# MODULO_TECLADO.net
KiCad netlist of a schematic drawn in EAGLE
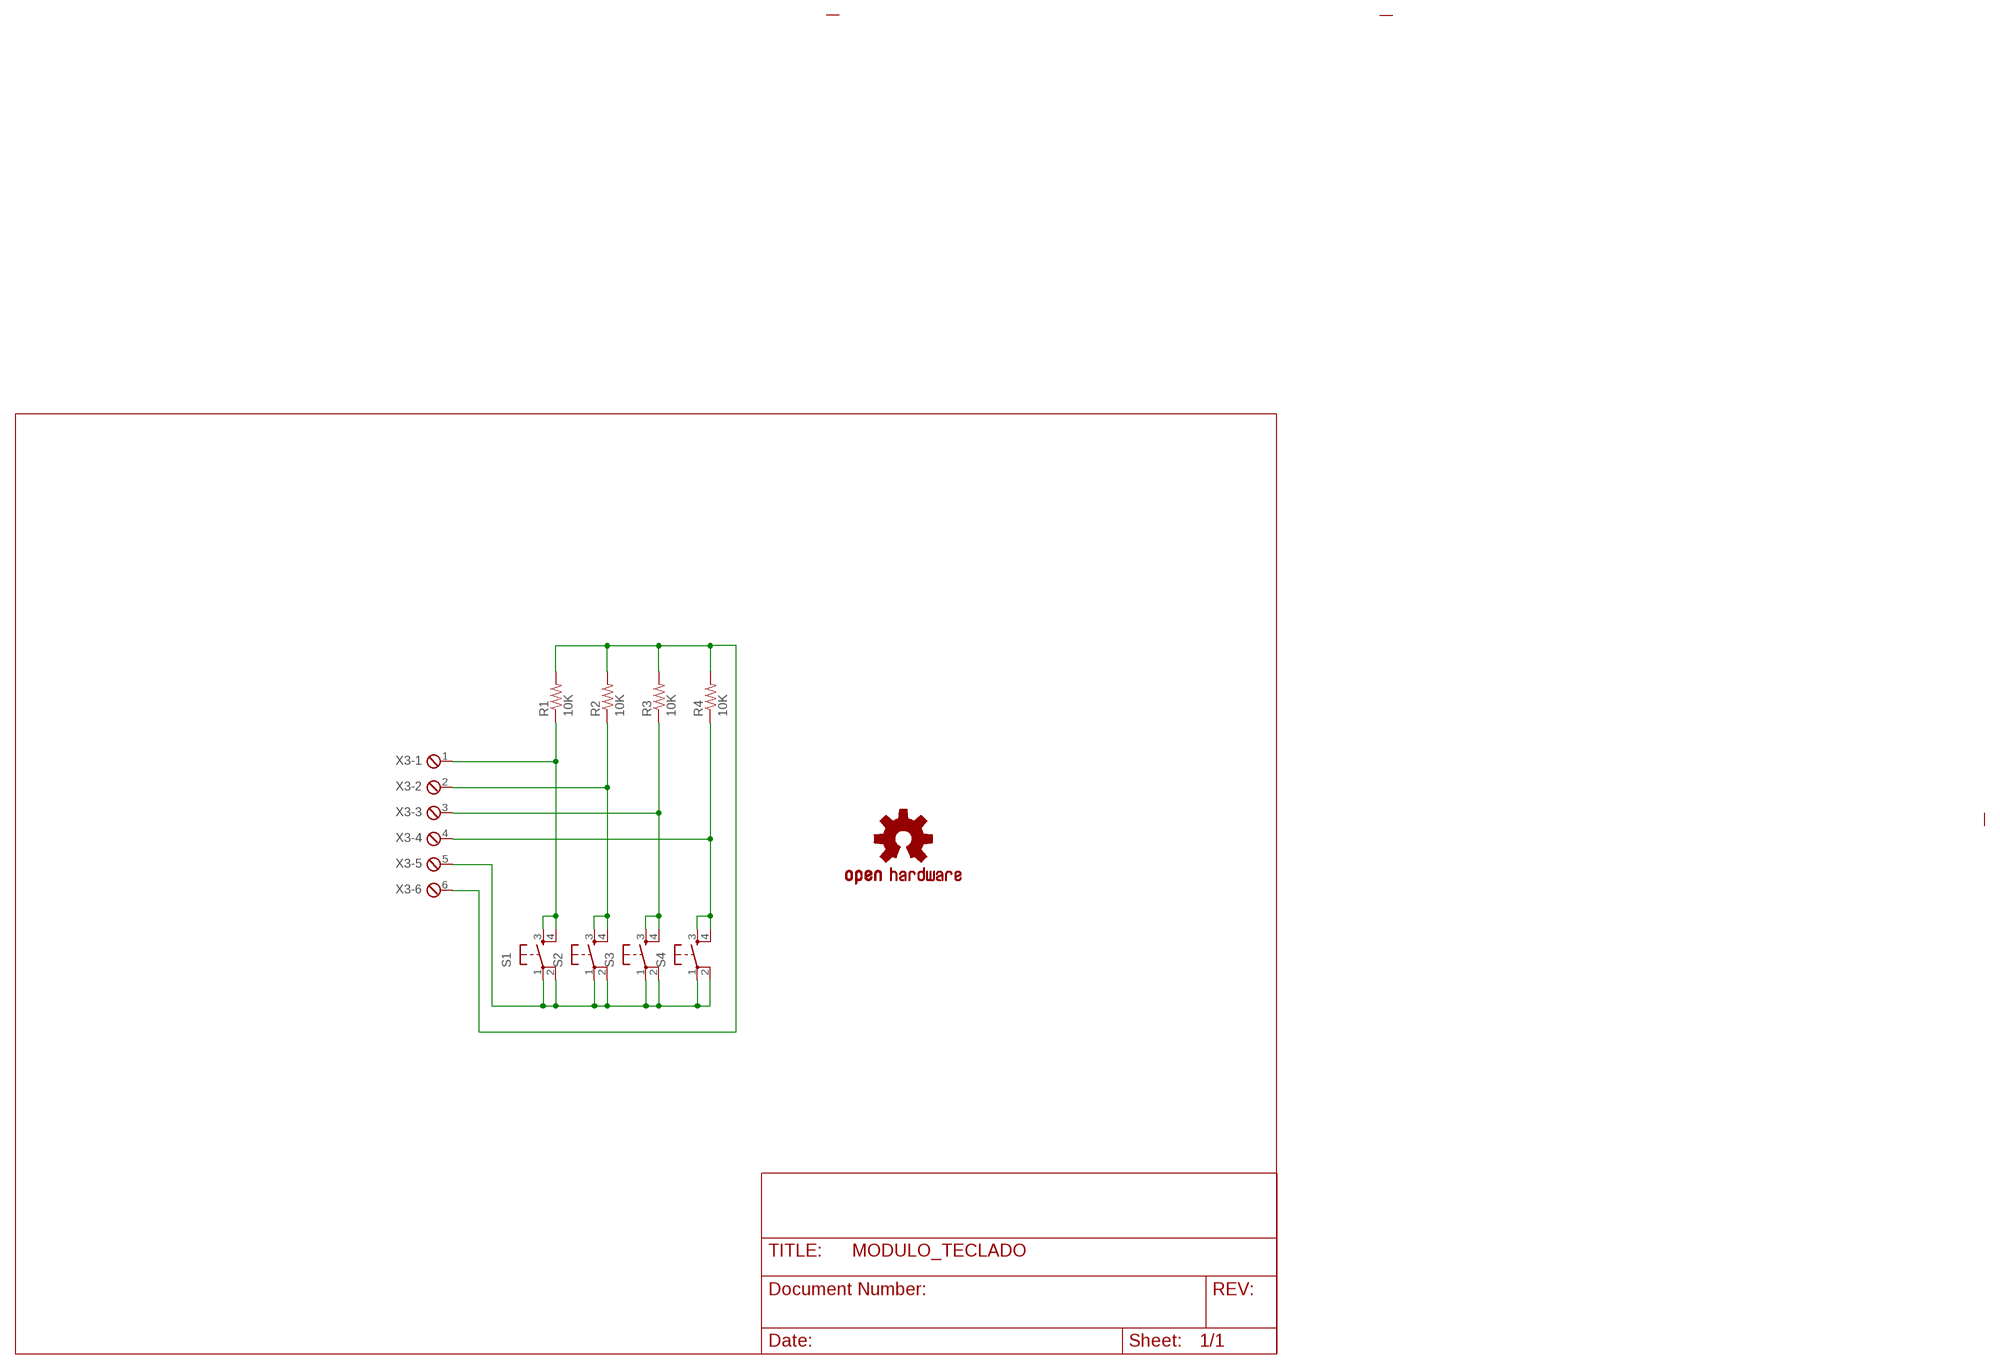
[diagram p0: schematic, sheet 1]

(export (version "E")
  (design (tool "Eeschema 10.0.6"))
  (components
    (comp (ref "LOGO1")
      (value "OSHW-LOGOL")
      (footprint "eagle-import:OSHW-LOGO-L")
      (libsource (lib "eagle-import") (part "OSHW-LOGOL"))
    )
    (comp (ref "R1")
      (value "10K")
      (footprint "eagle-import:AXIAL-0.4")
      (libsource (lib "eagle-import") (part "RESISTORPTH-1/4W"))
    )
    (comp (ref "R2")
      (value "10K")
      (footprint "eagle-import:AXIAL-0.4")
      (libsource (lib "eagle-import") (part "RESISTORPTH-1/4W"))
    )
    (comp (ref "R3")
      (value "10K")
      (footprint "eagle-import:AXIAL-0.4")
      (libsource (lib "eagle-import") (part "RESISTORPTH-1/4W"))
    )
    (comp (ref "R4")
      (value "10K")
      (footprint "eagle-import:AXIAL-0.4")
      (libsource (lib "eagle-import") (part "RESISTORPTH-1/4W"))
    )
    (comp (ref "S1")
      (value "TAC_SWITCHPTH")
      (footprint "eagle-import:TACTILE-PTH")
      (libsource (lib "eagle-import") (part "TAC_SWITCHPTH"))
    )
    (comp (ref "S2")
      (value "TAC_SWITCHPTH")
      (footprint "eagle-import:TACTILE-PTH")
      (libsource (lib "eagle-import") (part "TAC_SWITCHPTH"))
    )
    (comp (ref "S3")
      (value "TAC_SWITCHPTH")
      (footprint "eagle-import:TACTILE-PTH")
      (libsource (lib "eagle-import") (part "TAC_SWITCHPTH"))
    )
    (comp (ref "S4")
      (value "TAC_SWITCHPTH")
      (footprint "eagle-import:TACTILE-PTH")
      (libsource (lib "eagle-import") (part "TAC_SWITCHPTH"))
    )
    (comp (ref "X3")
      (value "MPT6")
      (footprint "eagle-import:6POL254")
      (libsource (lib "eagle-import") (part "MPT6"))
    )
  )
  (nets
    (net (code "1") (name "Net-(R1-1)") (class "Default")
      (node (ref "R1") (pin "P$1") (pinfunction "1_P$1") (pintype "passive"))
      (node (ref "S1") (pin "3") (pinfunction "3_3") (pintype "passive"))
      (node (ref "S1") (pin "4") (pinfunction "4_4") (pintype "passive"))
      (node (ref "X3") (pin "1") (pinfunction "1_1") (pintype "passive"))
    )
    (net (code "2") (name "Net-(R1-2)") (class "Default")
      (node (ref "R1") (pin "P$2") (pinfunction "2_P$2") (pintype "passive"))
      (node (ref "R2") (pin "P$2") (pinfunction "2_P$2") (pintype "passive"))
      (node (ref "R3") (pin "P$2") (pinfunction "2_P$2") (pintype "passive"))
      (node (ref "R4") (pin "P$2") (pinfunction "2_P$2") (pintype "passive"))
      (node (ref "X3") (pin "6") (pinfunction "1_6") (pintype "passive"))
    )
    (net (code "3") (name "Net-(R2-1)") (class "Default")
      (node (ref "R2") (pin "P$1") (pinfunction "1_P$1") (pintype "passive"))
      (node (ref "S2") (pin "3") (pinfunction "3_3") (pintype "passive"))
      (node (ref "S2") (pin "4") (pinfunction "4_4") (pintype "passive"))
      (node (ref "X3") (pin "2") (pinfunction "1_2") (pintype "passive"))
    )
    (net (code "4") (name "Net-(R3-1)") (class "Default")
      (node (ref "R3") (pin "P$1") (pinfunction "1_P$1") (pintype "passive"))
      (node (ref "S3") (pin "3") (pinfunction "3_3") (pintype "passive"))
      (node (ref "S3") (pin "4") (pinfunction "4_4") (pintype "passive"))
      (node (ref "X3") (pin "3") (pinfunction "1_3") (pintype "passive"))
    )
    (net (code "5") (name "Net-(R4-1)") (class "Default")
      (node (ref "R4") (pin "P$1") (pinfunction "1_P$1") (pintype "passive"))
      (node (ref "S4") (pin "3") (pinfunction "3_3") (pintype "passive"))
      (node (ref "S4") (pin "4") (pinfunction "4_4") (pintype "passive"))
      (node (ref "X3") (pin "4") (pinfunction "1_4") (pintype "passive"))
    )
    (net (code "6") (name "Net-(X3E-1)") (class "Default")
      (node (ref "S1") (pin "1") (pinfunction "1_1") (pintype "passive"))
      (node (ref "S1") (pin "2") (pinfunction "2_2") (pintype "passive"))
      (node (ref "S2") (pin "1") (pinfunction "1_1") (pintype "passive"))
      (node (ref "S2") (pin "2") (pinfunction "2_2") (pintype "passive"))
      (node (ref "S3") (pin "1") (pinfunction "1_1") (pintype "passive"))
      (node (ref "S3") (pin "2") (pinfunction "2_2") (pintype "passive"))
      (node (ref "S4") (pin "1") (pinfunction "1_1") (pintype "passive"))
      (node (ref "S4") (pin "2") (pinfunction "2_2") (pintype "passive"))
      (node (ref "X3") (pin "5") (pinfunction "1_5") (pintype "passive"))
    )
  )
)
